# motor-control-board.net
KiCad netlist of a schematic drawn in EAGLE
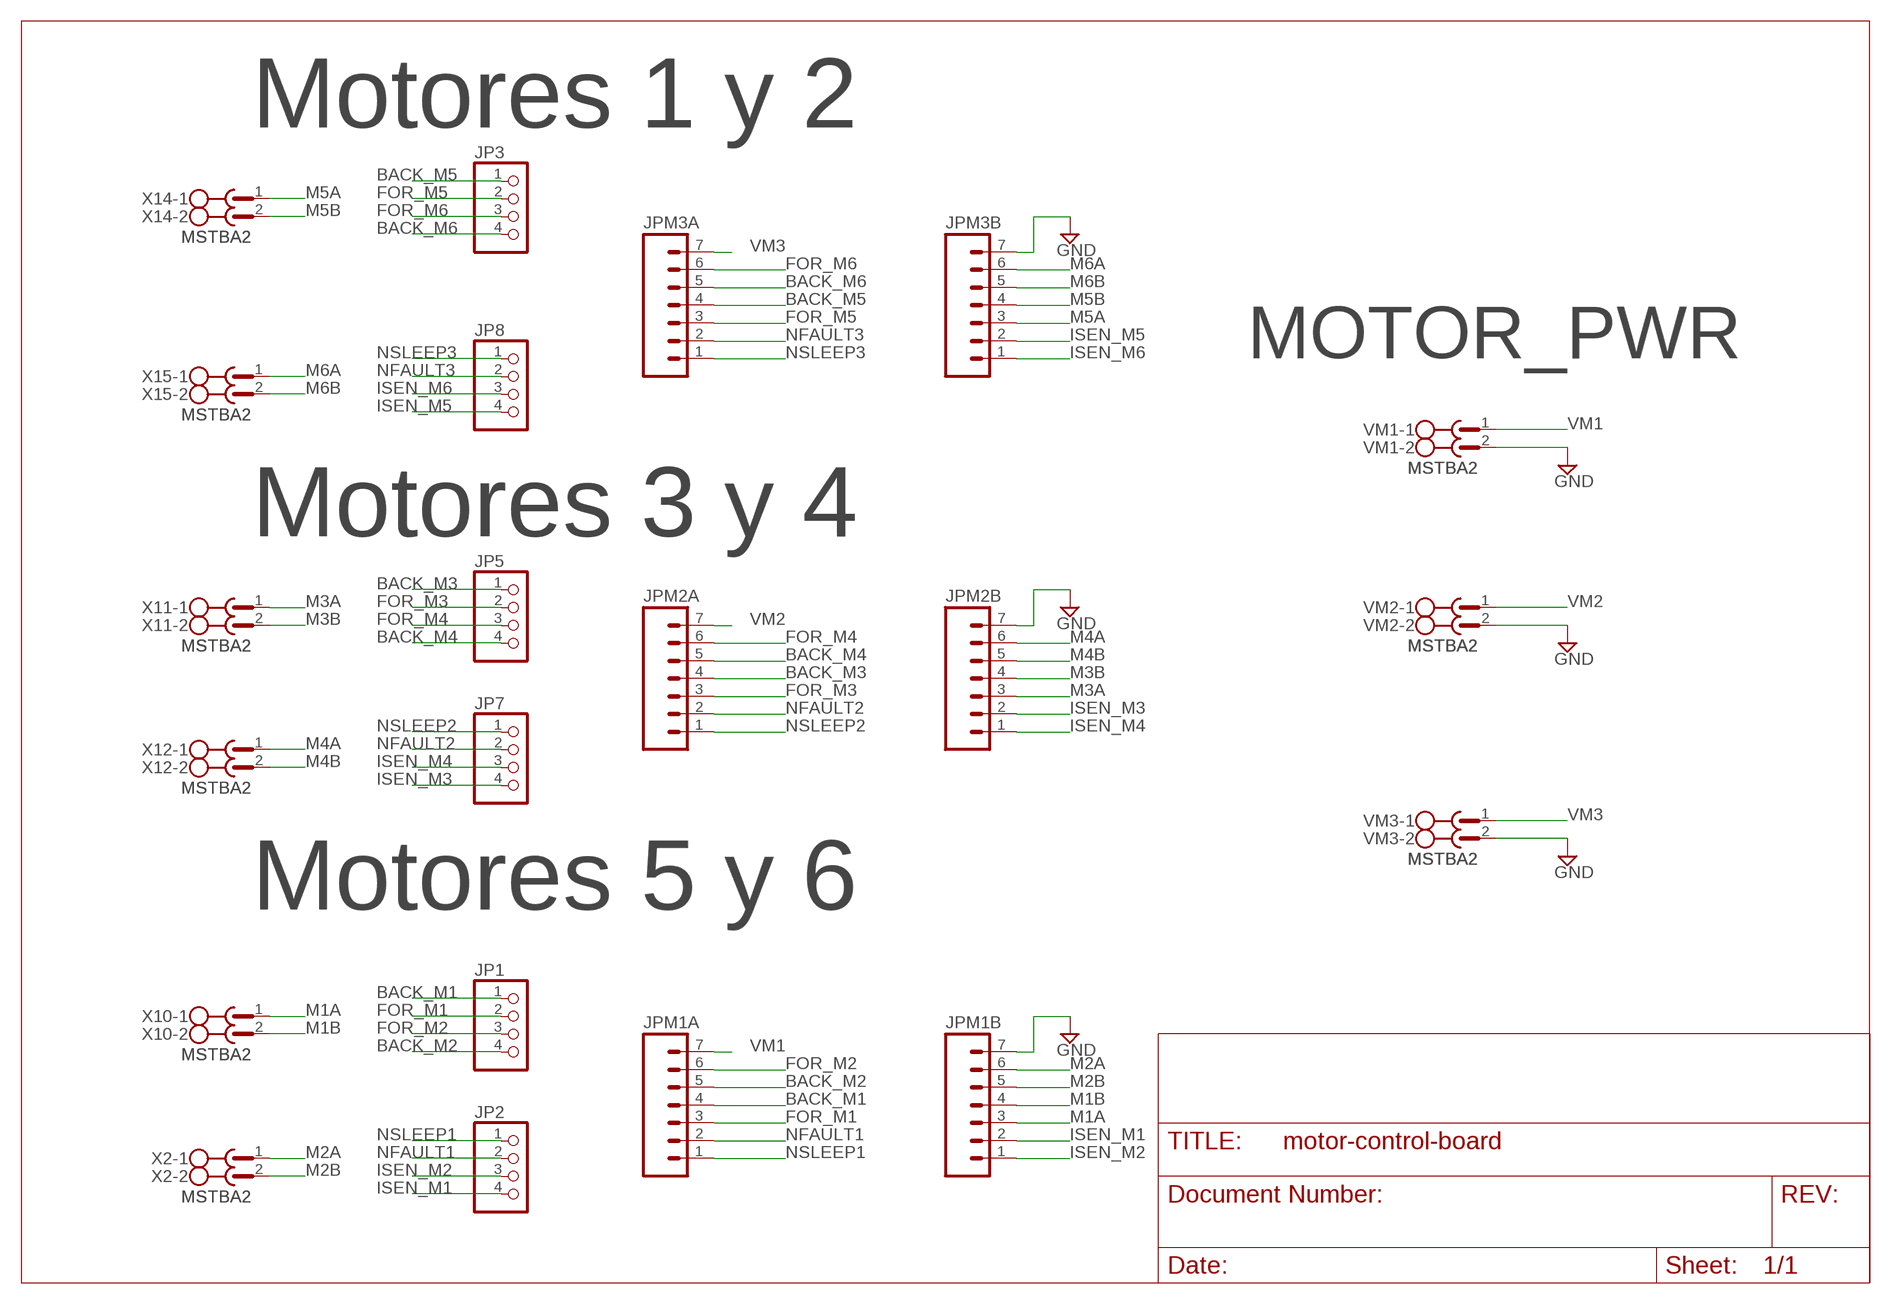
[diagram p0: schematic, sheet 1]

(export (version "E")
  (design (tool "Eeschema 10.0.6"))
  (components
    (comp (ref "JP1")
      (value "PINHD-1X4")
      (footprint "eagle-import:1X04")
      (libsource (lib "eagle-import") (part "PINHD-1X4"))
    )
    (comp (ref "JP2")
      (value "PINHD-1X4")
      (footprint "eagle-import:1X04")
      (libsource (lib "eagle-import") (part "PINHD-1X4"))
    )
    (comp (ref "JP3")
      (value "PINHD-1X4")
      (footprint "eagle-import:1X04")
      (libsource (lib "eagle-import") (part "PINHD-1X4"))
    )
    (comp (ref "JP5")
      (value "PINHD-1X4")
      (footprint "eagle-import:1X04")
      (libsource (lib "eagle-import") (part "PINHD-1X4"))
    )
    (comp (ref "JP7")
      (value "PINHD-1X4")
      (footprint "eagle-import:1X04")
      (libsource (lib "eagle-import") (part "PINHD-1X4"))
    )
    (comp (ref "JP8")
      (value "PINHD-1X4")
      (footprint "eagle-import:1X04")
      (libsource (lib "eagle-import") (part "PINHD-1X4"))
    )
    (comp (ref "JPM1A")
      (value "M07")
      (footprint "eagle-import:1X07")
      (libsource (lib "eagle-import") (part "M07"))
    )
    (comp (ref "JPM1B")
      (value "M07")
      (footprint "eagle-import:1X07")
      (libsource (lib "eagle-import") (part "M07"))
    )
    (comp (ref "JPM2A")
      (value "M07")
      (footprint "eagle-import:1X07")
      (libsource (lib "eagle-import") (part "M07"))
    )
    (comp (ref "JPM2B")
      (value "M07")
      (footprint "eagle-import:1X07")
      (libsource (lib "eagle-import") (part "M07"))
    )
    (comp (ref "JPM3A")
      (value "M07")
      (footprint "eagle-import:1X07")
      (libsource (lib "eagle-import") (part "M07"))
    )
    (comp (ref "JPM3B")
      (value "M07")
      (footprint "eagle-import:1X07")
      (libsource (lib "eagle-import") (part "M07"))
    )
    (comp (ref "VM1")
      (value "MSTBA2")
      (footprint "eagle-import:MSTBA2")
      (libsource (lib "eagle-import") (part "MSTBA2"))
    )
    (comp (ref "VM2")
      (value "MSTBA2")
      (footprint "eagle-import:MSTBA2")
      (libsource (lib "eagle-import") (part "MSTBA2"))
    )
    (comp (ref "VM3")
      (value "MSTBA2")
      (footprint "eagle-import:MSTBA2")
      (libsource (lib "eagle-import") (part "MSTBA2"))
    )
    (comp (ref "X2")
      (value "MSTBA2")
      (footprint "eagle-import:MSTBA2")
      (libsource (lib "eagle-import") (part "MSTBA2"))
    )
    (comp (ref "X10")
      (value "MSTBA2")
      (footprint "eagle-import:MSTBA2")
      (libsource (lib "eagle-import") (part "MSTBA2"))
    )
    (comp (ref "X11")
      (value "MSTBA2")
      (footprint "eagle-import:MSTBA2")
      (libsource (lib "eagle-import") (part "MSTBA2"))
    )
    (comp (ref "X12")
      (value "MSTBA2")
      (footprint "eagle-import:MSTBA2")
      (libsource (lib "eagle-import") (part "MSTBA2"))
    )
    (comp (ref "X14")
      (value "MSTBA2")
      (footprint "eagle-import:MSTBA2")
      (libsource (lib "eagle-import") (part "MSTBA2"))
    )
    (comp (ref "X15")
      (value "MSTBA2")
      (footprint "eagle-import:MSTBA2")
      (libsource (lib "eagle-import") (part "MSTBA2"))
    )
  )
  (nets
    (net (code "1") (name "/BACK_M1") (class "Default")
      (node (ref "JP1") (pin "1") (pinfunction "1_1") (pintype "passive"))
      (node (ref "JPM1A") (pin "4") (pinfunction "4_4") (pintype "passive"))
    )
    (net (code "2") (name "/BACK_M2") (class "Default")
      (node (ref "JP1") (pin "4") (pinfunction "4_4") (pintype "passive"))
      (node (ref "JPM1A") (pin "5") (pinfunction "5_5") (pintype "passive"))
    )
    (net (code "3") (name "/BACK_M3") (class "Default")
      (node (ref "JP5") (pin "1") (pinfunction "1_1") (pintype "passive"))
      (node (ref "JPM2A") (pin "4") (pinfunction "4_4") (pintype "passive"))
    )
    (net (code "4") (name "/BACK_M4") (class "Default")
      (node (ref "JP5") (pin "4") (pinfunction "4_4") (pintype "passive"))
      (node (ref "JPM2A") (pin "5") (pinfunction "5_5") (pintype "passive"))
    )
    (net (code "5") (name "/BACK_M5") (class "Default")
      (node (ref "JP3") (pin "1") (pinfunction "1_1") (pintype "passive"))
      (node (ref "JPM3A") (pin "4") (pinfunction "4_4") (pintype "passive"))
    )
    (net (code "6") (name "/BACK_M6") (class "Default")
      (node (ref "JP3") (pin "4") (pinfunction "4_4") (pintype "passive"))
      (node (ref "JPM3A") (pin "5") (pinfunction "5_5") (pintype "passive"))
    )
    (net (code "7") (name "/FOR_M1") (class "Default")
      (node (ref "JP1") (pin "2") (pinfunction "2_2") (pintype "passive"))
      (node (ref "JPM1A") (pin "3") (pinfunction "3_3") (pintype "passive"))
    )
    (net (code "8") (name "/FOR_M2") (class "Default")
      (node (ref "JP1") (pin "3") (pinfunction "3_3") (pintype "passive"))
      (node (ref "JPM1A") (pin "6") (pinfunction "6_6") (pintype "passive"))
    )
    (net (code "9") (name "/FOR_M3") (class "Default")
      (node (ref "JP5") (pin "2") (pinfunction "2_2") (pintype "passive"))
      (node (ref "JPM2A") (pin "3") (pinfunction "3_3") (pintype "passive"))
    )
    (net (code "10") (name "/FOR_M4") (class "Default")
      (node (ref "JP5") (pin "3") (pinfunction "3_3") (pintype "passive"))
      (node (ref "JPM2A") (pin "6") (pinfunction "6_6") (pintype "passive"))
    )
    (net (code "11") (name "/FOR_M5") (class "Default")
      (node (ref "JP3") (pin "2") (pinfunction "2_2") (pintype "passive"))
      (node (ref "JPM3A") (pin "3") (pinfunction "3_3") (pintype "passive"))
    )
    (net (code "12") (name "/FOR_M6") (class "Default")
      (node (ref "JP3") (pin "3") (pinfunction "3_3") (pintype "passive"))
      (node (ref "JPM3A") (pin "6") (pinfunction "6_6") (pintype "passive"))
    )
    (net (code "13") (name "/ISEN_M1") (class "Default")
      (node (ref "JP2") (pin "4") (pinfunction "4_4") (pintype "passive"))
      (node (ref "JPM1B") (pin "2") (pinfunction "2_2") (pintype "passive"))
    )
    (net (code "14") (name "/ISEN_M2") (class "Default")
      (node (ref "JP2") (pin "3") (pinfunction "3_3") (pintype "passive"))
      (node (ref "JPM1B") (pin "1") (pinfunction "1_1") (pintype "passive"))
    )
    (net (code "15") (name "/ISEN_M3") (class "Default")
      (node (ref "JP7") (pin "4") (pinfunction "4_4") (pintype "passive"))
      (node (ref "JPM2B") (pin "2") (pinfunction "2_2") (pintype "passive"))
    )
    (net (code "16") (name "/ISEN_M4") (class "Default")
      (node (ref "JP7") (pin "3") (pinfunction "3_3") (pintype "passive"))
      (node (ref "JPM2B") (pin "1") (pinfunction "1_1") (pintype "passive"))
    )
    (net (code "17") (name "/ISEN_M5") (class "Default")
      (node (ref "JP8") (pin "4") (pinfunction "4_4") (pintype "passive"))
      (node (ref "JPM3B") (pin "2") (pinfunction "2_2") (pintype "passive"))
    )
    (net (code "18") (name "/ISEN_M6") (class "Default")
      (node (ref "JP8") (pin "3") (pinfunction "3_3") (pintype "passive"))
      (node (ref "JPM3B") (pin "1") (pinfunction "1_1") (pintype "passive"))
    )
    (net (code "19") (name "/M1A") (class "Default")
      (node (ref "JPM1B") (pin "3") (pinfunction "3_3") (pintype "passive"))
      (node (ref "X10") (pin "1") (pinfunction "1_1") (pintype "passive"))
    )
    (net (code "20") (name "/M1B") (class "Default")
      (node (ref "JPM1B") (pin "4") (pinfunction "4_4") (pintype "passive"))
      (node (ref "X10") (pin "2") (pinfunction "1_2") (pintype "passive"))
    )
    (net (code "21") (name "/M2A") (class "Default")
      (node (ref "JPM1B") (pin "6") (pinfunction "6_6") (pintype "passive"))
      (node (ref "X2") (pin "1") (pinfunction "1_1") (pintype "passive"))
    )
    (net (code "22") (name "/M2B") (class "Default")
      (node (ref "JPM1B") (pin "5") (pinfunction "5_5") (pintype "passive"))
      (node (ref "X2") (pin "2") (pinfunction "1_2") (pintype "passive"))
    )
    (net (code "23") (name "/M3A") (class "Default")
      (node (ref "JPM2B") (pin "3") (pinfunction "3_3") (pintype "passive"))
      (node (ref "X11") (pin "1") (pinfunction "1_1") (pintype "passive"))
    )
    (net (code "24") (name "/M3B") (class "Default")
      (node (ref "JPM2B") (pin "4") (pinfunction "4_4") (pintype "passive"))
      (node (ref "X11") (pin "2") (pinfunction "1_2") (pintype "passive"))
    )
    (net (code "25") (name "/M4A") (class "Default")
      (node (ref "JPM2B") (pin "6") (pinfunction "6_6") (pintype "passive"))
      (node (ref "X12") (pin "1") (pinfunction "1_1") (pintype "passive"))
    )
    (net (code "26") (name "/M4B") (class "Default")
      (node (ref "JPM2B") (pin "5") (pinfunction "5_5") (pintype "passive"))
      (node (ref "X12") (pin "2") (pinfunction "1_2") (pintype "passive"))
    )
    (net (code "27") (name "/M5A") (class "Default")
      (node (ref "JPM3B") (pin "3") (pinfunction "3_3") (pintype "passive"))
      (node (ref "X14") (pin "1") (pinfunction "1_1") (pintype "passive"))
    )
    (net (code "28") (name "/M5B") (class "Default")
      (node (ref "JPM3B") (pin "4") (pinfunction "4_4") (pintype "passive"))
      (node (ref "X14") (pin "2") (pinfunction "1_2") (pintype "passive"))
    )
    (net (code "29") (name "/M6A") (class "Default")
      (node (ref "JPM3B") (pin "6") (pinfunction "6_6") (pintype "passive"))
      (node (ref "X15") (pin "1") (pinfunction "1_1") (pintype "passive"))
    )
    (net (code "30") (name "/M6B") (class "Default")
      (node (ref "JPM3B") (pin "5") (pinfunction "5_5") (pintype "passive"))
      (node (ref "X15") (pin "2") (pinfunction "1_2") (pintype "passive"))
    )
    (net (code "31") (name "/NFAULT1") (class "Default")
      (node (ref "JP2") (pin "2") (pinfunction "2_2") (pintype "passive"))
      (node (ref "JPM1A") (pin "2") (pinfunction "2_2") (pintype "passive"))
    )
    (net (code "32") (name "/NFAULT2") (class "Default")
      (node (ref "JP7") (pin "2") (pinfunction "2_2") (pintype "passive"))
      (node (ref "JPM2A") (pin "2") (pinfunction "2_2") (pintype "passive"))
    )
    (net (code "33") (name "/NFAULT3") (class "Default")
      (node (ref "JP8") (pin "2") (pinfunction "2_2") (pintype "passive"))
      (node (ref "JPM3A") (pin "2") (pinfunction "2_2") (pintype "passive"))
    )
    (net (code "34") (name "/NSLEEP1") (class "Default")
      (node (ref "JP2") (pin "1") (pinfunction "1_1") (pintype "passive"))
      (node (ref "JPM1A") (pin "1") (pinfunction "1_1") (pintype "passive"))
    )
    (net (code "35") (name "/NSLEEP2") (class "Default")
      (node (ref "JP7") (pin "1") (pinfunction "1_1") (pintype "passive"))
      (node (ref "JPM2A") (pin "1") (pinfunction "1_1") (pintype "passive"))
    )
    (net (code "36") (name "/NSLEEP3") (class "Default")
      (node (ref "JP8") (pin "1") (pinfunction "1_1") (pintype "passive"))
      (node (ref "JPM3A") (pin "1") (pinfunction "1_1") (pintype "passive"))
    )
    (net (code "37") (name "/VM1") (class "Default")
      (node (ref "JPM1A") (pin "7") (pinfunction "7_7") (pintype "passive"))
      (node (ref "VM1") (pin "1") (pinfunction "1_1") (pintype "passive"))
    )
    (net (code "38") (name "/VM2") (class "Default")
      (node (ref "JPM2A") (pin "7") (pinfunction "7_7") (pintype "passive"))
      (node (ref "VM2") (pin "1") (pinfunction "1_1") (pintype "passive"))
    )
    (net (code "39") (name "/VM3") (class "Default")
      (node (ref "JPM3A") (pin "7") (pinfunction "7_7") (pintype "passive"))
      (node (ref "VM3") (pin "1") (pinfunction "1_1") (pintype "passive"))
    )
    (net (code "40") (name "GND") (class "Default")
      (node (ref "JPM1B") (pin "7") (pinfunction "7_7") (pintype "passive"))
      (node (ref "JPM2B") (pin "7") (pinfunction "7_7") (pintype "passive"))
      (node (ref "JPM3B") (pin "7") (pinfunction "7_7") (pintype "passive"))
      (node (ref "VM1") (pin "2") (pinfunction "1_2") (pintype "passive"))
      (node (ref "VM2") (pin "2") (pinfunction "1_2") (pintype "passive"))
      (node (ref "VM3") (pin "2") (pinfunction "1_2") (pintype "passive"))
    )
  )
)
